# Lab5_TB_Sheet1.net
KiCad netlist of a schematic drawn in Altium Designer
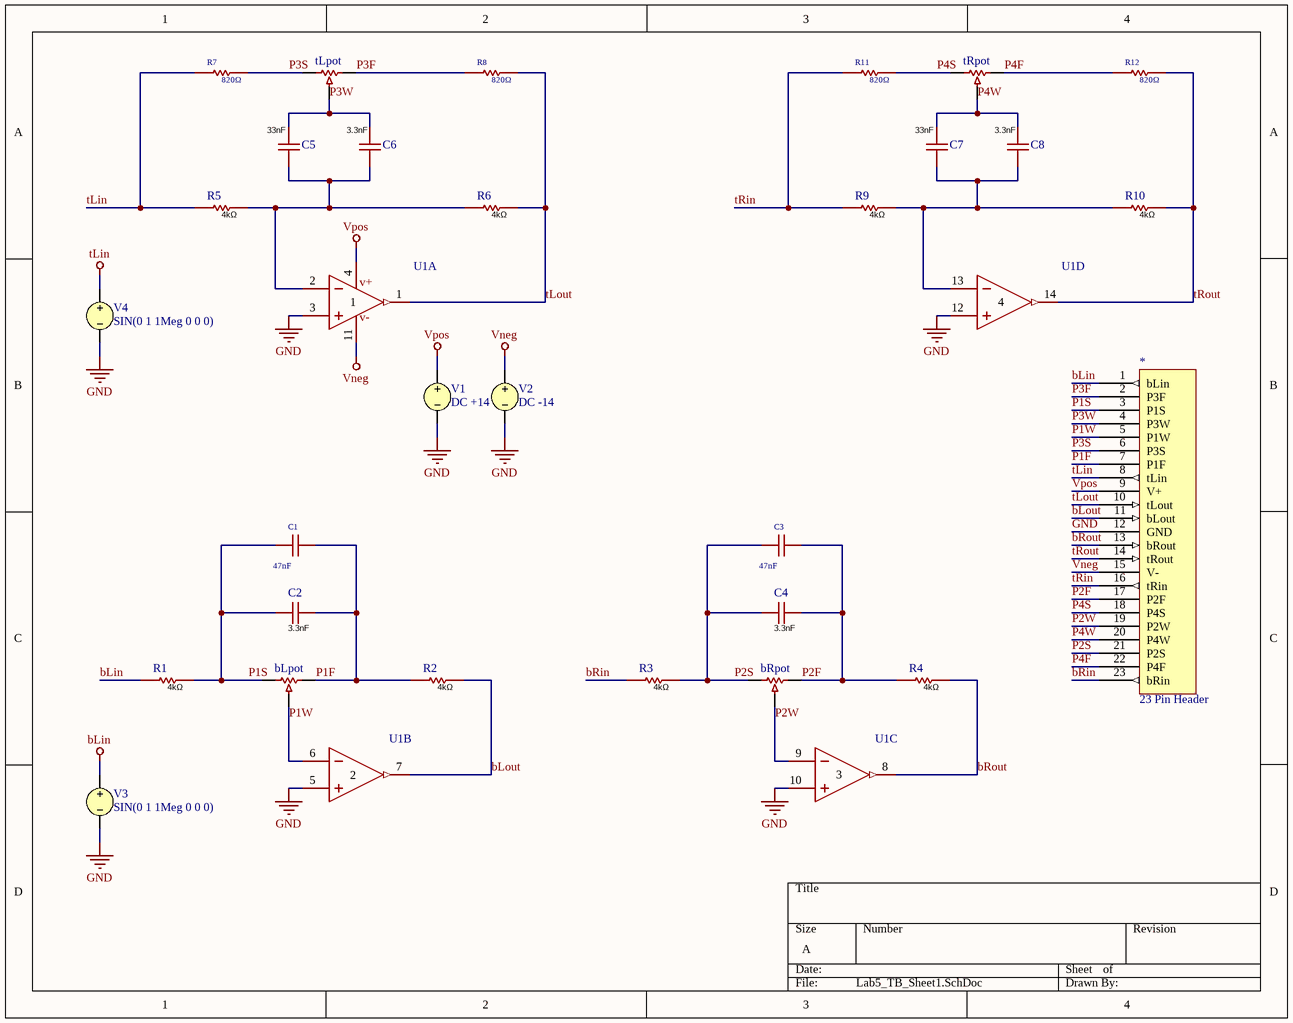
[diagram p0: Lab5_TB_Sheet1.SchDoc]

(export (version "E")
  (design (tool "Eeschema 10.0.6"))
  (components
    (comp (ref "*")
      (value "23 Pin Header")
      (footprint "KBS_23pin_Header_TB_EQ")
      (libsource (lib "ECEN299_JLC_Library") (part "23 Pin Header"))
    )
    (comp (ref "bLpot") (value "kbs_pot") (libsource (lib "ECEN299_JLC_Library") (part "kbs_pot")))
    (comp (ref "bRpot") (value "kbs_pot") (libsource (lib "ECEN299_JLC_Library") (part "kbs_pot")))
    (comp (ref "C1")
      (value "47nF")
      (footprint "C1206")
      (fields
        (field (name "MANUFACTURER PART") "GRM31M5C1H473JA01L")
        (field (name "MANUFACTURER") "muRata(村田)")
        (field (name "TOLERANCE") "±5%")
      )
      (libsource (lib "ECEN299_JLC_Library") (part "GRM31M5C1H473JA01L"))
    )
    (comp (ref "C2")
      (value "3.3nF")
      (footprint "C0805")
      (fields
        (field (name "MANUFACTURER") "FH(风华)")
        (field (name "MANUFACTURER PART") "0805B332K500NT")
        (field (name "TOLERANCE") "±10%")
      )
      (libsource (lib "ECEN299_JLC_Library") (part "0805B332K500NT"))
    )
    (comp (ref "C3")
      (value "47nF")
      (footprint "C1206")
      (fields
        (field (name "MANUFACTURER PART") "GRM31M5C1H473JA01L")
        (field (name "MANUFACTURER") "muRata(村田)")
        (field (name "TOLERANCE") "±5%")
      )
      (libsource (lib "ECEN299_JLC_Library") (part "GRM31M5C1H473JA01L"))
    )
    (comp (ref "C4")
      (value "3.3nF")
      (footprint "C0805")
      (fields
        (field (name "MANUFACTURER") "FH(风华)")
        (field (name "MANUFACTURER PART") "0805B332K500NT")
        (field (name "TOLERANCE") "±10%")
      )
      (libsource (lib "ECEN299_JLC_Library") (part "0805B332K500NT"))
    )
    (comp (ref "C5")
      (value "33nF")
      (footprint "C0805")
      (fields
        (field (name "MANUFACTURER") "FH(风华)")
        (field (name "MANUFACTURER PART") "0805B333K500NT")
        (field (name "TOLERANCE") "±10%")
      )
      (libsource (lib "ECEN299_JLC_Library") (part "0805B333K500NT"))
    )
    (comp (ref "C6")
      (value "3.3nF")
      (footprint "C0805")
      (fields
        (field (name "MANUFACTURER") "FH(风华)")
        (field (name "MANUFACTURER PART") "0805B332K500NT")
        (field (name "TOLERANCE") "±10%")
      )
      (libsource (lib "ECEN299_JLC_Library") (part "0805B332K500NT"))
    )
    (comp (ref "C7")
      (value "33nF")
      (footprint "C0805")
      (fields
        (field (name "MANUFACTURER") "FH(风华)")
        (field (name "MANUFACTURER PART") "0805B333K500NT")
        (field (name "TOLERANCE") "±10%")
      )
      (libsource (lib "ECEN299_JLC_Library") (part "0805B333K500NT"))
    )
    (comp (ref "C8")
      (value "3.3nF")
      (footprint "C0805")
      (fields
        (field (name "MANUFACTURER") "FH(风华)")
        (field (name "MANUFACTURER PART") "0805B332K500NT")
        (field (name "TOLERANCE") "±10%")
      )
      (libsource (lib "ECEN299_JLC_Library") (part "0805B332K500NT"))
    )
    (comp (ref "R1")
      (value "4kΩ")
      (footprint "R0805")
      (fields
        (field (name "MANUFACTURER") "Viking(光颉)")
        (field (name "MANUFACTURER PART") "ARG05FTC4001N")
        (field (name "TOLERANCE") "±1%")
      )
      (libsource (lib "ECEN299_JLC_Library") (part "ARG05FTC4001N"))
    )
    (comp (ref "R2")
      (value "4kΩ")
      (footprint "R0805")
      (fields
        (field (name "MANUFACTURER") "Viking(光颉)")
        (field (name "MANUFACTURER PART") "ARG05FTC4001N")
        (field (name "TOLERANCE") "±1%")
      )
      (libsource (lib "ECEN299_JLC_Library") (part "ARG05FTC4001N"))
    )
    (comp (ref "R3")
      (value "4kΩ")
      (footprint "R0805")
      (fields
        (field (name "MANUFACTURER") "Viking(光颉)")
        (field (name "MANUFACTURER PART") "ARG05FTC4001N")
        (field (name "TOLERANCE") "±1%")
      )
      (libsource (lib "ECEN299_JLC_Library") (part "ARG05FTC4001N"))
    )
    (comp (ref "R4")
      (value "4kΩ")
      (footprint "R0805")
      (fields
        (field (name "MANUFACTURER") "Viking(光颉)")
        (field (name "MANUFACTURER PART") "ARG05FTC4001N")
        (field (name "TOLERANCE") "±1%")
      )
      (libsource (lib "ECEN299_JLC_Library") (part "ARG05FTC4001N"))
    )
    (comp (ref "R5")
      (value "4kΩ")
      (footprint "R0805")
      (fields
        (field (name "MANUFACTURER") "Viking(光颉)")
        (field (name "MANUFACTURER PART") "ARG05FTC4001N")
        (field (name "TOLERANCE") "±1%")
      )
      (libsource (lib "ECEN299_JLC_Library") (part "ARG05FTC4001N"))
    )
    (comp (ref "R6")
      (value "4kΩ")
      (footprint "R0805")
      (fields
        (field (name "MANUFACTURER") "Viking(光颉)")
        (field (name "MANUFACTURER PART") "ARG05FTC4001N")
        (field (name "TOLERANCE") "±1%")
      )
      (libsource (lib "ECEN299_JLC_Library") (part "ARG05FTC4001N"))
    )
    (comp (ref "R7")
      (value "820Ω")
      (footprint "R0603")
      (fields
        (field (name "MANUFACTURER") "UNI-ROYAL(厚声)")
        (field (name "MANUFACTURER PART") "0603WAF8200T5E")
        (field (name "TOLERANCE") "±1%")
      )
      (libsource (lib "ECEN299_JLC_Library") (part "0603WAF8200T5E"))
    )
    (comp (ref "R8")
      (value "820Ω")
      (footprint "R0603")
      (fields
        (field (name "MANUFACTURER") "UNI-ROYAL(厚声)")
        (field (name "MANUFACTURER PART") "0603WAF8200T5E")
        (field (name "TOLERANCE") "±1%")
      )
      (libsource (lib "ECEN299_JLC_Library") (part "0603WAF8200T5E"))
    )
    (comp (ref "R9")
      (value "4kΩ")
      (footprint "R0805")
      (fields
        (field (name "MANUFACTURER") "Viking(光颉)")
        (field (name "MANUFACTURER PART") "ARG05FTC4001N")
        (field (name "TOLERANCE") "±1%")
      )
      (libsource (lib "ECEN299_JLC_Library") (part "ARG05FTC4001N"))
    )
    (comp (ref "R10")
      (value "4kΩ")
      (footprint "R0805")
      (fields
        (field (name "MANUFACTURER") "Viking(光颉)")
        (field (name "MANUFACTURER PART") "ARG05FTC4001N")
        (field (name "TOLERANCE") "±1%")
      )
      (libsource (lib "ECEN299_JLC_Library") (part "ARG05FTC4001N"))
    )
    (comp (ref "R11")
      (value "820Ω")
      (footprint "R0603")
      (fields
        (field (name "MANUFACTURER") "UNI-ROYAL(厚声)")
        (field (name "MANUFACTURER PART") "0603WAF8200T5E")
        (field (name "TOLERANCE") "±1%")
      )
      (libsource (lib "ECEN299_JLC_Library") (part "0603WAF8200T5E"))
    )
    (comp (ref "R12")
      (value "820Ω")
      (footprint "R0603")
      (fields
        (field (name "MANUFACTURER") "UNI-ROYAL(厚声)")
        (field (name "MANUFACTURER PART") "0603WAF8200T5E")
        (field (name "TOLERANCE") "±1%")
      )
      (libsource (lib "ECEN299_JLC_Library") (part "0603WAF8200T5E"))
    )
    (comp (ref "tLpot") (value "kbs_pot") (libsource (lib "ECEN299_JLC_Library") (part "kbs_pot")))
    (comp (ref "tRpot") (value "kbs_pot") (libsource (lib "ECEN299_JLC_Library") (part "kbs_pot")))
    (comp (ref "U1")
      (value "LM324DT")
      (footprint "KBS_SO14_w_Guide_Pin_Holes")
      (fields (field (name "MANUFACTURER") "ST(意法半导体)"))
      (libsource (lib "ECEN299_JLC_Library") (part "LM324DT"))
    )
    (comp (ref "V1")
      (value "DC +14")
      (description "Voltage Source")
      (fields (field (name "PUBLISHER") "Altium Limited"))
      (libsource (lib "Simulation Generic Components") (part "VSRC"))
    )
    (comp (ref "V2")
      (value "DC -14")
      (description "Voltage Source")
      (fields (field (name "PUBLISHER") "Altium Limited"))
      (libsource (lib "Simulation Generic Components") (part "VSRC"))
    )
    (comp (ref "V3")
      (value "SIN(0 1 1Meg 0 0 0)")
      (description "Voltage Source")
      (fields (field (name "PUBLISHER") "Altium Limited"))
      (libsource (lib "Simulation Generic Components") (part "VSRC"))
    )
    (comp (ref "V4")
      (value "SIN(0 1 1Meg 0 0 0)")
      (description "Voltage Source")
      (fields (field (name "PUBLISHER") "Altium Limited"))
      (libsource (lib "Simulation Generic Components") (part "VSRC"))
    )
  )
  (nets
    (net (code "1") (name "/P1F") (class "Default")
      (node (ref "*") (pin "7") (pinfunction "P1F_7") (pintype "passive"))
      (node (ref "C1") (pin "2") (pinfunction "2_2") (pintype "passive"))
      (node (ref "C2") (pin "1") (pinfunction "1_1") (pintype "passive"))
      (node (ref "R2") (pin "1") (pinfunction "1_1") (pintype "passive"))
      (node (ref "bLpot") (pin "1") (pinfunction "End2_1") (pintype "passive"))
    )
    (net (code "2") (name "/P1S") (class "Default")
      (node (ref "*") (pin "3") (pinfunction "P1S_3") (pintype "passive"))
      (node (ref "C1") (pin "1") (pinfunction "1_1") (pintype "passive"))
      (node (ref "C2") (pin "2") (pinfunction "2_2") (pintype "passive"))
      (node (ref "R1") (pin "2") (pinfunction "2_2") (pintype "passive"))
      (node (ref "bLpot") (pin "0") (pinfunction "End1_0") (pintype "passive"))
    )
    (net (code "3") (name "/P1W") (class "Default")
      (node (ref "*") (pin "5") (pinfunction "P1W_5") (pintype "passive"))
      (node (ref "U1") (pin "6") (pinfunction "IN2-_6") (pintype "passive"))
      (node (ref "bLpot") (pin "2") (pinfunction "Wiper_2") (pintype "passive"))
    )
    (net (code "4") (name "/P2F") (class "Default")
      (node (ref "*") (pin "17") (pinfunction "P2F_17") (pintype "passive"))
      (node (ref "C3") (pin "2") (pinfunction "2_2") (pintype "passive"))
      (node (ref "C4") (pin "1") (pinfunction "1_1") (pintype "passive"))
      (node (ref "R4") (pin "1") (pinfunction "1_1") (pintype "passive"))
      (node (ref "bRpot") (pin "1") (pinfunction "End2_1") (pintype "passive"))
    )
    (net (code "5") (name "/P2S") (class "Default")
      (node (ref "*") (pin "21") (pinfunction "P2S_21") (pintype "passive"))
      (node (ref "C3") (pin "1") (pinfunction "1_1") (pintype "passive"))
      (node (ref "C4") (pin "2") (pinfunction "2_2") (pintype "passive"))
      (node (ref "R3") (pin "2") (pinfunction "2_2") (pintype "passive"))
      (node (ref "bRpot") (pin "0") (pinfunction "End1_0") (pintype "passive"))
    )
    (net (code "6") (name "/P2W") (class "Default")
      (node (ref "*") (pin "19") (pinfunction "P2W_19") (pintype "passive"))
      (node (ref "U1") (pin "9") (pinfunction "IN3-_9") (pintype "passive"))
      (node (ref "bRpot") (pin "2") (pinfunction "Wiper_2") (pintype "passive"))
    )
    (net (code "7") (name "/P3F") (class "Default")
      (node (ref "*") (pin "2") (pinfunction "P3F_2") (pintype "passive"))
      (node (ref "R8") (pin "1") (pinfunction "1_1") (pintype "passive"))
      (node (ref "tLpot") (pin "1") (pinfunction "End2_1") (pintype "passive"))
    )
    (net (code "8") (name "/P3S") (class "Default")
      (node (ref "*") (pin "6") (pinfunction "P3S_6") (pintype "passive"))
      (node (ref "R7") (pin "2") (pinfunction "2_2") (pintype "passive"))
      (node (ref "tLpot") (pin "0") (pinfunction "End1_0") (pintype "passive"))
    )
    (net (code "9") (name "/P3W") (class "Default")
      (node (ref "*") (pin "4") (pinfunction "P3W_4") (pintype "passive"))
      (node (ref "C5") (pin "2") (pinfunction "2_2") (pintype "passive"))
      (node (ref "C6") (pin "2") (pinfunction "2_2") (pintype "passive"))
      (node (ref "tLpot") (pin "2") (pinfunction "Wiper_2") (pintype "passive"))
    )
    (net (code "10") (name "/P4F") (class "Default")
      (node (ref "*") (pin "22") (pinfunction "P4F_22") (pintype "passive"))
      (node (ref "R12") (pin "1") (pinfunction "1_1") (pintype "passive"))
      (node (ref "tRpot") (pin "1") (pinfunction "End2_1") (pintype "passive"))
    )
    (net (code "11") (name "/P4S") (class "Default")
      (node (ref "*") (pin "18") (pinfunction "P4S_18") (pintype "passive"))
      (node (ref "R11") (pin "2") (pinfunction "2_2") (pintype "passive"))
      (node (ref "tRpot") (pin "0") (pinfunction "End1_0") (pintype "passive"))
    )
    (net (code "12") (name "/P4W") (class "Default")
      (node (ref "*") (pin "20") (pinfunction "P4W_20") (pintype "passive"))
      (node (ref "C7") (pin "2") (pinfunction "2_2") (pintype "passive"))
      (node (ref "C8") (pin "2") (pinfunction "2_2") (pintype "passive"))
      (node (ref "tRpot") (pin "2") (pinfunction "Wiper_2") (pintype "passive"))
    )
    (net (code "13") (name "/bLout") (class "Default")
      (node (ref "*") (pin "11") (pinfunction "bLout_11") (pintype "input"))
      (node (ref "R2") (pin "2") (pinfunction "2_2") (pintype "passive"))
      (node (ref "U1") (pin "7") (pinfunction "OUT2_7") (pintype "output"))
    )
    (net (code "14") (name "/bRin") (class "Default")
      (node (ref "*") (pin "23") (pinfunction "bRin_23") (pintype "output"))
      (node (ref "R3") (pin "1") (pinfunction "1_1") (pintype "passive"))
    )
    (net (code "15") (name "/bRout") (class "Default")
      (node (ref "*") (pin "13") (pinfunction "bRout_13") (pintype "input"))
      (node (ref "R4") (pin "2") (pinfunction "2_2") (pintype "passive"))
      (node (ref "U1") (pin "8") (pinfunction "OUT3_8") (pintype "output"))
    )
    (net (code "16") (name "/tLout") (class "Default")
      (node (ref "*") (pin "10") (pinfunction "tLout_10") (pintype "input"))
      (node (ref "R6") (pin "2") (pinfunction "2_2") (pintype "passive"))
      (node (ref "R8") (pin "2") (pinfunction "2_2") (pintype "passive"))
      (node (ref "U1") (pin "1") (pinfunction "OUT1_1") (pintype "output"))
    )
    (net (code "17") (name "/tRin") (class "Default")
      (node (ref "*") (pin "16") (pinfunction "tRin_16") (pintype "output"))
      (node (ref "R11") (pin "1") (pinfunction "1_1") (pintype "passive"))
      (node (ref "R9") (pin "1") (pinfunction "1_1") (pintype "passive"))
    )
    (net (code "18") (name "/tRout") (class "Default")
      (node (ref "*") (pin "14") (pinfunction "tRout_14") (pintype "input"))
      (node (ref "R10") (pin "2") (pinfunction "2_2") (pintype "passive"))
      (node (ref "R12") (pin "2") (pinfunction "2_2") (pintype "passive"))
      (node (ref "U1") (pin "14") (pinfunction "OUT4_14") (pintype "output"))
    )
    (net (code "19") (name "GND") (class "Default")
      (node (ref "*") (pin "12") (pinfunction "GND_12") (pintype "power_in"))
      (node (ref "U1") (pin "10") (pinfunction "IN3+_10") (pintype "passive"))
      (node (ref "U1") (pin "12") (pinfunction "IN4+_12") (pintype "passive"))
      (node (ref "U1") (pin "3") (pinfunction "IN1+_3") (pintype "passive"))
      (node (ref "U1") (pin "5") (pinfunction "IN2+_5") (pintype "passive"))
      (node (ref "V1") (pin "2") (pinfunction "2_2") (pintype "passive"))
      (node (ref "V2") (pin "2") (pinfunction "2_2") (pintype "passive"))
      (node (ref "V3") (pin "2") (pinfunction "2_2") (pintype "passive"))
      (node (ref "V4") (pin "2") (pinfunction "2_2") (pintype "passive"))
    )
    (net (code "20") (name "Net-(U1A-IN1-)") (class "Default")
      (node (ref "C5") (pin "1") (pinfunction "1_1") (pintype "passive"))
      (node (ref "C6") (pin "1") (pinfunction "1_1") (pintype "passive"))
      (node (ref "R5") (pin "2") (pinfunction "2_2") (pintype "passive"))
      (node (ref "R6") (pin "1") (pinfunction "1_1") (pintype "passive"))
      (node (ref "U1") (pin "2") (pinfunction "IN1-_2") (pintype "passive"))
    )
    (net (code "21") (name "Net-(U1D-IN4-)") (class "Default")
      (node (ref "C7") (pin "1") (pinfunction "1_1") (pintype "passive"))
      (node (ref "C8") (pin "1") (pinfunction "1_1") (pintype "passive"))
      (node (ref "R10") (pin "1") (pinfunction "1_1") (pintype "passive"))
      (node (ref "R9") (pin "2") (pinfunction "2_2") (pintype "passive"))
      (node (ref "U1") (pin "13") (pinfunction "IN4-_13") (pintype "passive"))
    )
    (net (code "22") (name "Vneg") (class "Default")
      (node (ref "*") (pin "15") (pinfunction "V-_15") (pintype "power_in"))
      (node (ref "U1") (pin "11") (pinfunction "VCC-_11") (pintype "power_in"))
      (node (ref "V2") (pin "1") (pinfunction "1_1") (pintype "passive"))
    )
    (net (code "23") (name "Vpos") (class "Default")
      (node (ref "*") (pin "9") (pinfunction "V+_9") (pintype "power_in"))
      (node (ref "U1") (pin "4") (pinfunction "VCC+_4") (pintype "power_in"))
      (node (ref "V1") (pin "1") (pinfunction "1_1") (pintype "passive"))
    )
    (net (code "24") (name "bLin") (class "Default")
      (node (ref "*") (pin "1") (pinfunction "bLin_1") (pintype "output"))
      (node (ref "R1") (pin "1") (pinfunction "1_1") (pintype "passive"))
      (node (ref "V3") (pin "1") (pinfunction "1_1") (pintype "passive"))
    )
    (net (code "25") (name "tLin") (class "Default")
      (node (ref "*") (pin "8") (pinfunction "tLin_8") (pintype "output"))
      (node (ref "R5") (pin "1") (pinfunction "1_1") (pintype "passive"))
      (node (ref "R7") (pin "1") (pinfunction "1_1") (pintype "passive"))
      (node (ref "V4") (pin "1") (pinfunction "1_1") (pintype "passive"))
    )
  )
)
